# Gnd_iso.net
KiCad netlist of a schematic drawn in EAGLE
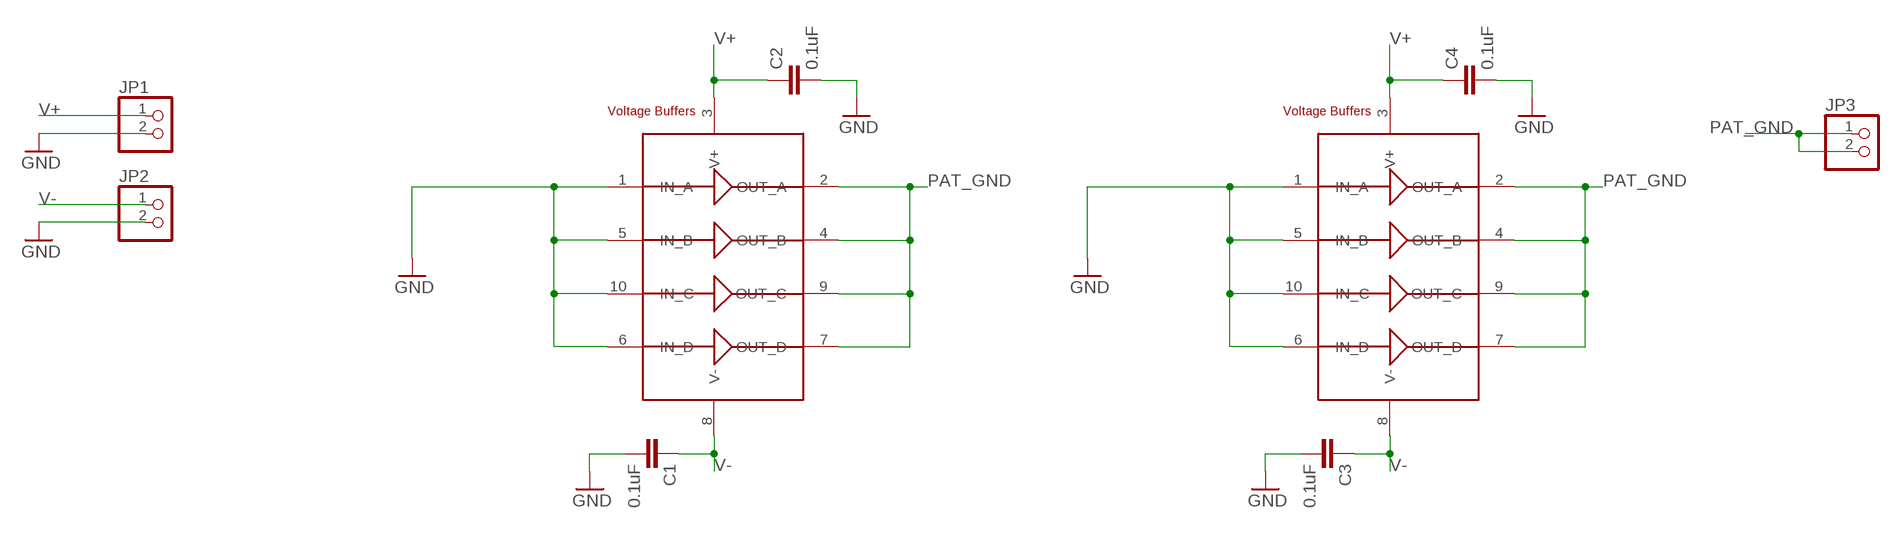
[diagram p0: schematic, sheet 1]

(export (version "E")
  (design (tool "Eeschema 10.0.6"))
  (components
    (comp (ref "C1")
      (value "0.1uF")
      (footprint "eagle-import:C0805")
      (libsource (lib "eagle-import") (part "C-EUC0805"))
    )
    (comp (ref "C2")
      (value "0.1uF")
      (footprint "eagle-import:C0805")
      (libsource (lib "eagle-import") (part "C-EUC0805"))
    )
    (comp (ref "C3")
      (value "0.1uF")
      (footprint "eagle-import:C0805")
      (libsource (lib "eagle-import") (part "C-EUC0805"))
    )
    (comp (ref "C4")
      (value "0.1uF")
      (footprint "eagle-import:C0805")
      (libsource (lib "eagle-import") (part "C-EUC0805"))
    )
    (comp (ref "JP1")
      (value "PINHD-1X2/90")
      (footprint "eagle-import:1X02_90")
      (libsource (lib "eagle-import") (part "PINHD-1X2/90"))
    )
    (comp (ref "JP2")
      (value "PINHD-1X2/90")
      (footprint "eagle-import:1X02_90")
      (libsource (lib "eagle-import") (part "PINHD-1X2/90"))
    )
    (comp (ref "JP3")
      (value "PINHD-1X2/90")
      (footprint "eagle-import:1X02_90")
      (libsource (lib "eagle-import") (part "PINHD-1X2/90"))
    )
    (comp (ref "U1")
      (value "AD8244")
      (footprint "eagle-import:MSOP10")
      (libsource (lib "eagle-import") (part "AD8244"))
    )
    (comp (ref "U2")
      (value "AD8244")
      (footprint "eagle-import:MSOP10")
      (libsource (lib "eagle-import") (part "AD8244"))
    )
  )
  (nets
    (net (code "1") (name "/PAT_GND") (class "Default")
      (node (ref "JP3") (pin "1") (pinfunction "1_1") (pintype "passive"))
      (node (ref "JP3") (pin "2") (pinfunction "2_2") (pintype "passive"))
      (node (ref "U1") (pin "2") (pinfunction "OUT_A_2") (pintype "bidirectional"))
      (node (ref "U1") (pin "4") (pinfunction "OUT_B_4") (pintype "bidirectional"))
      (node (ref "U1") (pin "7") (pinfunction "OUT_D_7") (pintype "bidirectional"))
      (node (ref "U1") (pin "9") (pinfunction "OUT_C_9") (pintype "bidirectional"))
      (node (ref "U2") (pin "2") (pinfunction "OUT_A_2") (pintype "bidirectional"))
      (node (ref "U2") (pin "4") (pinfunction "OUT_B_4") (pintype "bidirectional"))
      (node (ref "U2") (pin "7") (pinfunction "OUT_D_7") (pintype "bidirectional"))
      (node (ref "U2") (pin "9") (pinfunction "OUT_C_9") (pintype "bidirectional"))
    )
    (net (code "2") (name "/V+") (class "Default")
      (node (ref "C2") (pin "1") (pinfunction "1_1") (pintype "passive"))
      (node (ref "C4") (pin "1") (pinfunction "1_1") (pintype "passive"))
      (node (ref "JP1") (pin "1") (pinfunction "1_1") (pintype "passive"))
      (node (ref "U1") (pin "3") (pinfunction "V+_3") (pintype "bidirectional"))
      (node (ref "U2") (pin "3") (pinfunction "V+_3") (pintype "bidirectional"))
    )
    (net (code "3") (name "/V-") (class "Default")
      (node (ref "C1") (pin "1") (pinfunction "1_1") (pintype "passive"))
      (node (ref "C3") (pin "1") (pinfunction "1_1") (pintype "passive"))
      (node (ref "JP2") (pin "1") (pinfunction "1_1") (pintype "passive"))
      (node (ref "U1") (pin "8") (pinfunction "V-_8") (pintype "bidirectional"))
      (node (ref "U2") (pin "8") (pinfunction "V-_8") (pintype "bidirectional"))
    )
    (net (code "4") (name "GND") (class "Default")
      (node (ref "C1") (pin "2") (pinfunction "2_2") (pintype "passive"))
      (node (ref "C2") (pin "2") (pinfunction "2_2") (pintype "passive"))
      (node (ref "C3") (pin "2") (pinfunction "2_2") (pintype "passive"))
      (node (ref "C4") (pin "2") (pinfunction "2_2") (pintype "passive"))
      (node (ref "JP1") (pin "2") (pinfunction "2_2") (pintype "passive"))
      (node (ref "JP2") (pin "2") (pinfunction "2_2") (pintype "passive"))
      (node (ref "U1") (pin "1") (pinfunction "IN_A_1") (pintype "bidirectional"))
      (node (ref "U1") (pin "10") (pinfunction "IN_C_10") (pintype "bidirectional"))
      (node (ref "U1") (pin "5") (pinfunction "IN_B_5") (pintype "bidirectional"))
      (node (ref "U1") (pin "6") (pinfunction "IN_D_6") (pintype "bidirectional"))
      (node (ref "U2") (pin "1") (pinfunction "IN_A_1") (pintype "bidirectional"))
      (node (ref "U2") (pin "10") (pinfunction "IN_C_10") (pintype "bidirectional"))
      (node (ref "U2") (pin "5") (pinfunction "IN_B_5") (pintype "bidirectional"))
      (node (ref "U2") (pin "6") (pinfunction "IN_D_6") (pintype "bidirectional"))
    )
  )
)
